# Environmental.net
KiCad netlist of a schematic drawn in Altium Designer
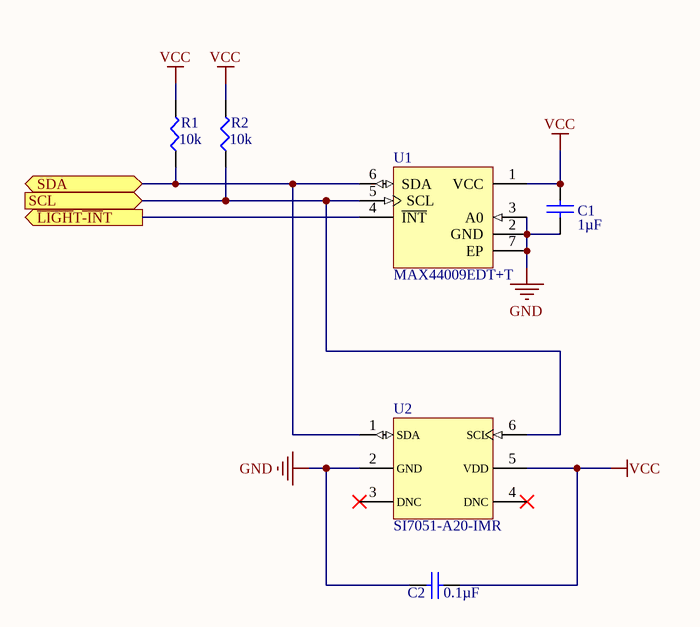
[diagram p0: Environmental.SchDoc]

(export (version "E")
  (design (tool "Eeschema 10.0.6"))
  (components
    (comp (ref "C1")
      (value "CL10B105KP8NFNC")
      (footprint "C0603N")
      (description "CAP CER 1UF 10V X7R 0603")
      (fields
        (field (name "HOUSEPART") "NO")
        (field (name "TOLERANCE") "±10%")
        (field (name "CAPACITANCE") "1µF")
      )
      (libsource (lib "MF_Passives") (part "CAPACITOR_NP"))
    )
    (comp (ref "C2")
      (value "CL10B104KO8NFNC")
      (footprint "C0603N")
      (fields
        (field (name "HOUSEPART") "NO")
        (field (name "TOLERANCE") "±10%")
        (field (name "VOLTAGE") "16V")
        (field (name "CAPACITANCE") "0.1µF")
      )
      (libsource (lib "MF_Passives") (part "CAPACITOR_NP"))
    )
    (comp (ref "R1")
      (value "10k")
      (footprint "SMD-0603-RES")
      (description "RES SMD 10K OHM 1% 1/10W 0603")
      (fields
        (field (name "PART NUMBER") "ERJ-3EKF1002V")
        (field (name "DIGI-KEY PART NUMBER") "P10.0KHCT-ND")
      )
      (libsource (lib "Panasonic_ERJ_0603") (part "ERJ-3EKF1002V"))
    )
    (comp (ref "R2")
      (value "10k")
      (footprint "SMD-0603-RES")
      (description "RES SMD 10K OHM 1% 1/10W 0603")
      (fields
        (field (name "PART NUMBER") "ERJ-3EKF1002V")
        (field (name "DIGI-KEY PART NUMBER") "P10.0KHCT-ND")
      )
      (libsource (lib "Panasonic_ERJ_0603") (part "ERJ-3EKF1002V"))
    )
    (comp (ref "U1")
      (value "MAX44009EDT+T")
      (footprint "21-0490D")
      (description "MAX44009 light sensor")
      (libsource (lib "max44009") (part "MAX44009EDT+T"))
    )
    (comp (ref "U2")
      (value "SI7051-A20-IMR")
      (footprint "si705x-hand")
      (description "Temperature Sensor tal, Local -40°C ~ 125°C 14 b 6-DFN (3x3)")
      (libsource (lib "SI705x") (part "CMP-6e6fa3261226b1a8-2"))
    )
  )
  (nets
    (net (code "1") (name "/SCL") (class "Default")
      (node (ref "R2") (pin "1") (pinfunction "1_1") (pintype "passive"))
      (node (ref "U1") (pin "5") (pinfunction "SCL_5") (pintype "input"))
      (node (ref "U2") (pin "6") (pinfunction "SCL_6") (pintype "input"))
    )
    (net (code "2") (name "/SDA") (class "Default")
      (node (ref "R1") (pin "1") (pinfunction "1_1") (pintype "passive"))
      (node (ref "U1") (pin "6") (pinfunction "SDA_6") (pintype "bidirectional"))
      (node (ref "U2") (pin "1") (pinfunction "SDA_1") (pintype "bidirectional"))
    )
    (net (code "3") (name "/~{LIGH}T~{-IN}T") (class "Default")
      (node (ref "U1") (pin "4") (pinfunction "~{INT}_4") (pintype "open_collector"))
    )
    (net (code "4") (name "GND") (class "Default")
      (node (ref "C1") (pin "1") (pinfunction "1_1") (pintype "passive"))
      (node (ref "C2") (pin "1") (pinfunction "1_1") (pintype "passive"))
      (node (ref "U1") (pin "2") (pinfunction "GND_2") (pintype "power_in"))
      (node (ref "U1") (pin "3") (pinfunction "A0_3") (pintype "input"))
      (node (ref "U1") (pin "7") (pinfunction "EP_7") (pintype "power_in"))
      (node (ref "U2") (pin "2") (pinfunction "GND_2") (pintype "power_in"))
    )
    (net (code "5") (name "VCC") (class "Default")
      (node (ref "C1") (pin "2") (pinfunction "2_2") (pintype "passive"))
      (node (ref "C2") (pin "2") (pinfunction "2_2") (pintype "passive"))
      (node (ref "R1") (pin "2") (pinfunction "2_2") (pintype "passive"))
      (node (ref "R2") (pin "2") (pinfunction "2_2") (pintype "passive"))
      (node (ref "U1") (pin "1") (pinfunction "VCC_1") (pintype "power_in"))
      (node (ref "U2") (pin "5") (pinfunction "VDD_5") (pintype "power_in"))
    )
    (net (code "6") (name "unconnected-(U2-DNC-Pad3)") (class "Default")
      (node (ref "U2") (pin "3") (pinfunction "DNC_3") (pintype "passive+no_connect"))
    )
    (net (code "7") (name "unconnected-(U2-DNC-Pad4)") (class "Default")
      (node (ref "U2") (pin "4") (pinfunction "DNC_4") (pintype "passive+no_connect"))
    )
  )
)
